# PillEndo-Proto_LED.net
KiCad netlist of a schematic drawn in EAGLE
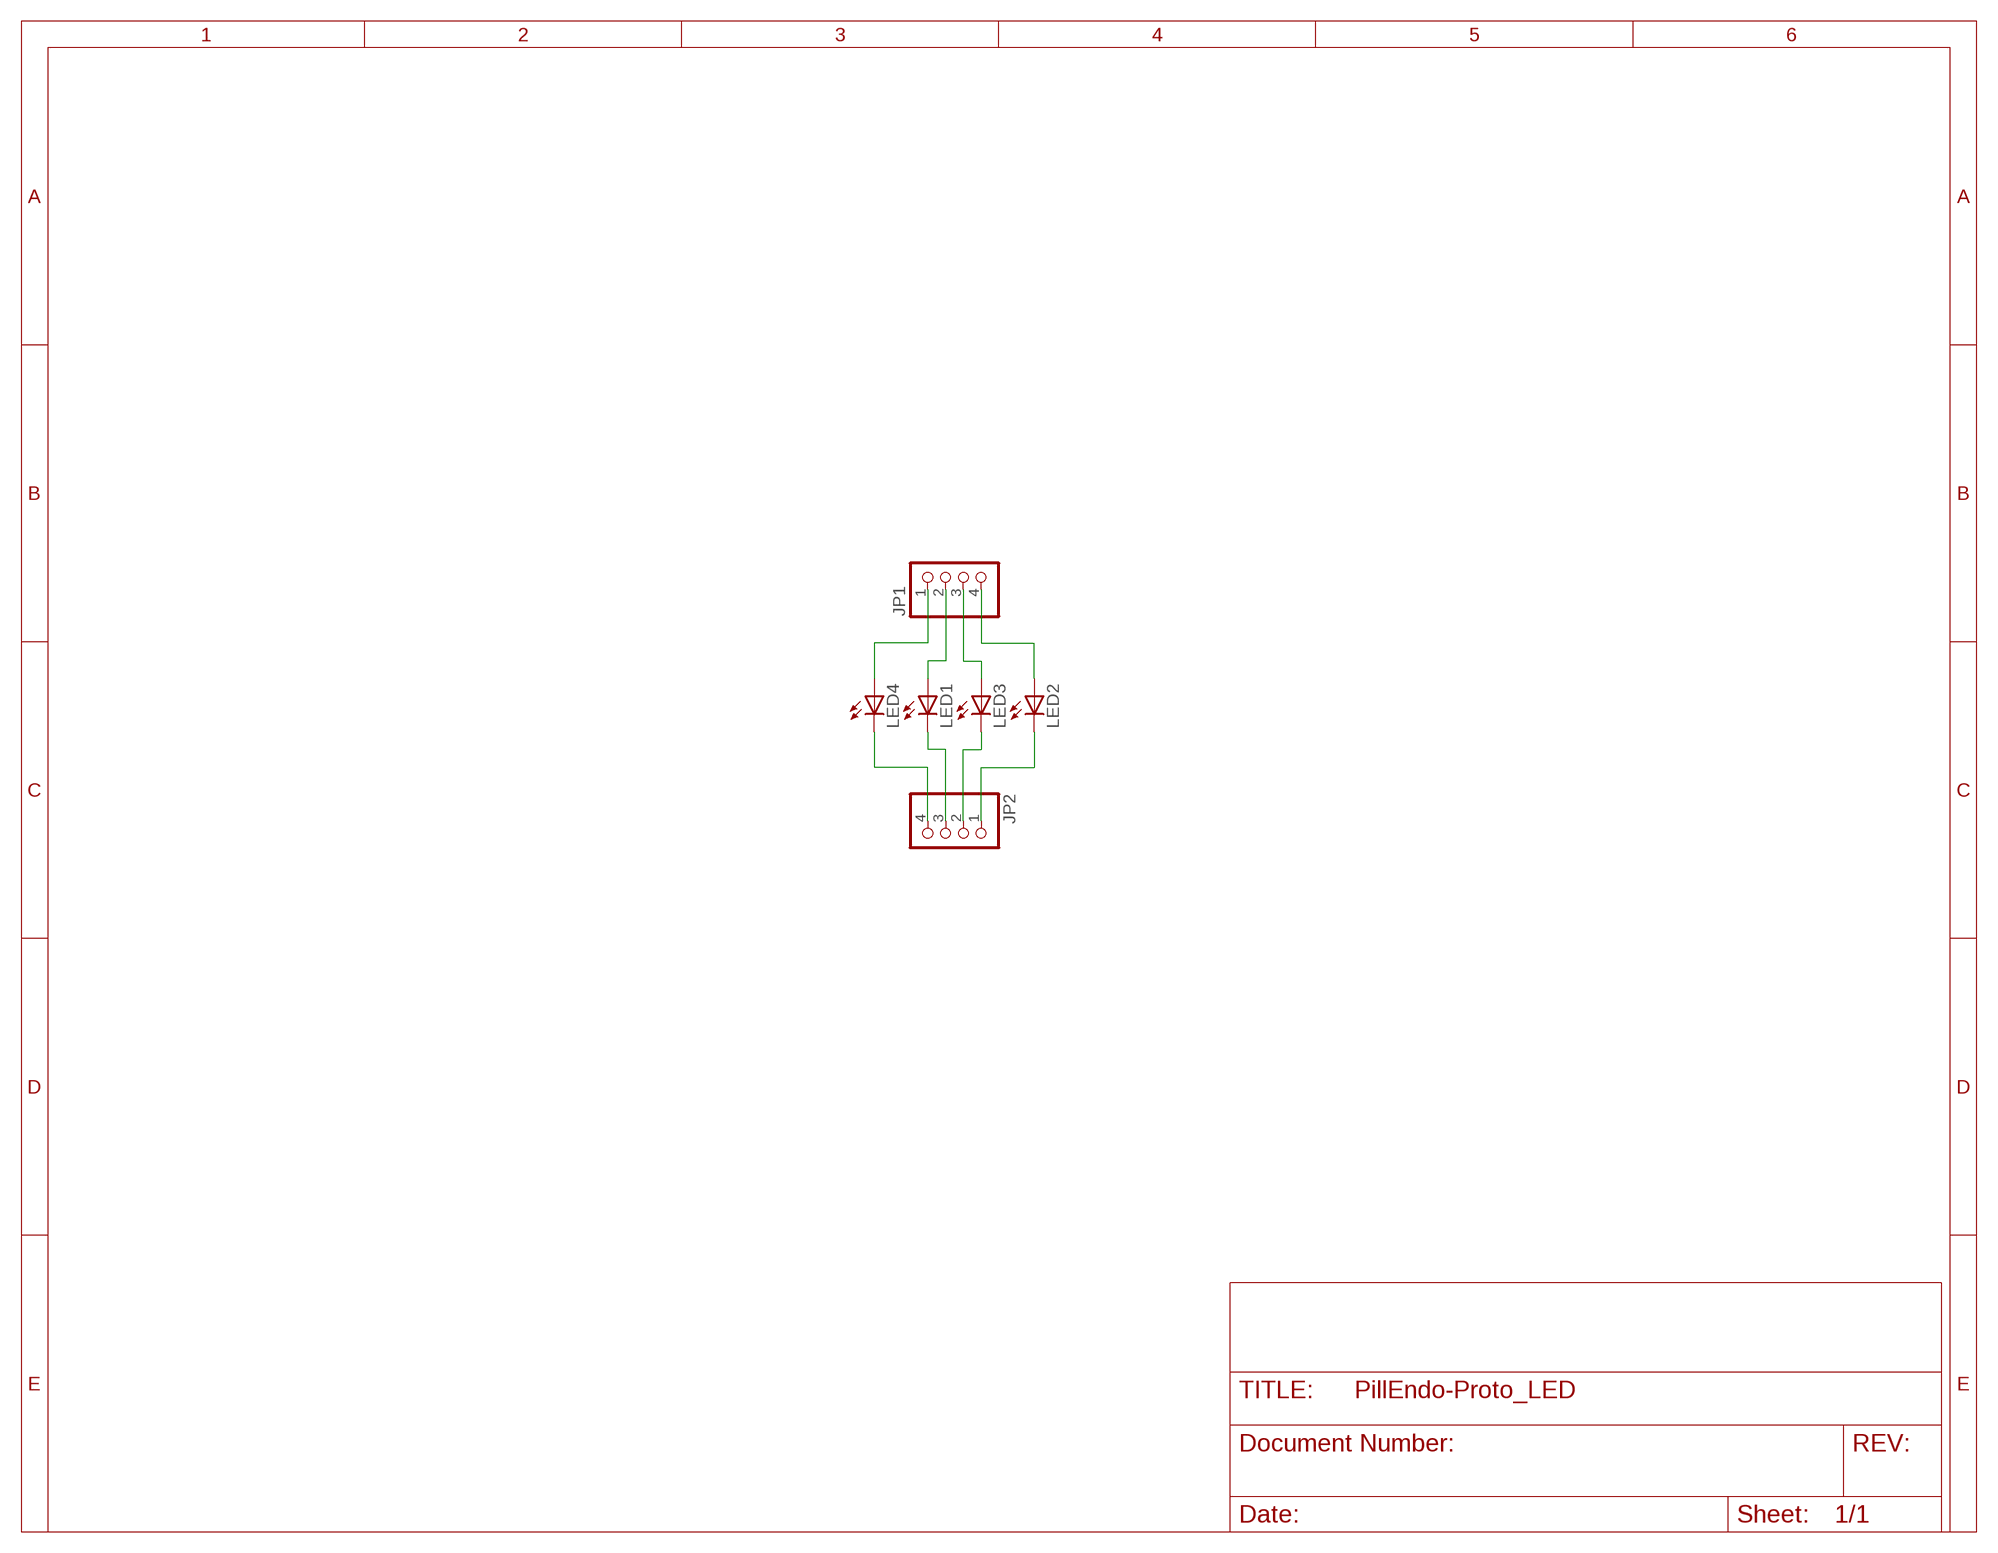
[diagram p0: schematic, sheet 1]

(export (version "E")
  (design (tool "Eeschema 10.0.6"))
  (components
    (comp (ref "JP1")
      (value "PINHD-1X4")
      (footprint "eagle-import:1X04")
      (libsource (lib "eagle-import") (part "PINHD-1X4"))
    )
    (comp (ref "JP2")
      (value "PINHD-1X4")
      (footprint "eagle-import:1X04")
      (libsource (lib "eagle-import") (part "PINHD-1X4"))
    )
    (comp (ref "LED1")
      (value "LED")
      (footprint "eagle-import:SMARTLED-TTW")
      (libsource (lib "eagle-import") (part "LED"))
    )
    (comp (ref "LED2")
      (value "LED")
      (footprint "eagle-import:SMARTLED-TTW")
      (libsource (lib "eagle-import") (part "LED"))
    )
    (comp (ref "LED3")
      (value "LED")
      (footprint "eagle-import:SMARTLED-TTW")
      (libsource (lib "eagle-import") (part "LED"))
    )
    (comp (ref "LED4")
      (value "LED")
      (footprint "eagle-import:SMARTLED-TTW")
      (libsource (lib "eagle-import") (part "LED"))
    )
  )
  (nets
    (net (code "1") (name "Net-(LED1-A)") (class "Default")
      (node (ref "JP1") (pin "2") (pinfunction "2_2") (pintype "passive"))
      (node (ref "LED1") (pin "A@1") (pinfunction "A_A@1") (pintype "passive"))
    )
    (net (code "2") (name "Net-(LED1-C)") (class "Default")
      (node (ref "JP2") (pin "3") (pinfunction "3_3") (pintype "passive"))
      (node (ref "LED1") (pin "C@1") (pinfunction "C_C@1") (pintype "passive"))
    )
    (net (code "3") (name "Net-(LED2-A)") (class "Default")
      (node (ref "JP1") (pin "4") (pinfunction "4_4") (pintype "passive"))
      (node (ref "LED2") (pin "A@1") (pinfunction "A_A@1") (pintype "passive"))
    )
    (net (code "4") (name "Net-(LED2-C)") (class "Default")
      (node (ref "JP2") (pin "1") (pinfunction "1_1") (pintype "passive"))
      (node (ref "LED2") (pin "C@1") (pinfunction "C_C@1") (pintype "passive"))
    )
    (net (code "5") (name "Net-(LED3-A)") (class "Default")
      (node (ref "JP1") (pin "3") (pinfunction "3_3") (pintype "passive"))
      (node (ref "LED3") (pin "A@1") (pinfunction "A_A@1") (pintype "passive"))
    )
    (net (code "6") (name "Net-(LED3-C)") (class "Default")
      (node (ref "JP2") (pin "2") (pinfunction "2_2") (pintype "passive"))
      (node (ref "LED3") (pin "C@1") (pinfunction "C_C@1") (pintype "passive"))
    )
    (net (code "7") (name "Net-(LED4-A)") (class "Default")
      (node (ref "JP1") (pin "1") (pinfunction "1_1") (pintype "passive"))
      (node (ref "LED4") (pin "A@1") (pinfunction "A_A@1") (pintype "passive"))
    )
    (net (code "8") (name "Net-(LED4-C)") (class "Default")
      (node (ref "JP2") (pin "4") (pinfunction "4_4") (pintype "passive"))
      (node (ref "LED4") (pin "C@1") (pinfunction "C_C@1") (pintype "passive"))
    )
  )
)
